# Power_Converter.net
KiCad netlist of a schematic drawn in Altium Designer
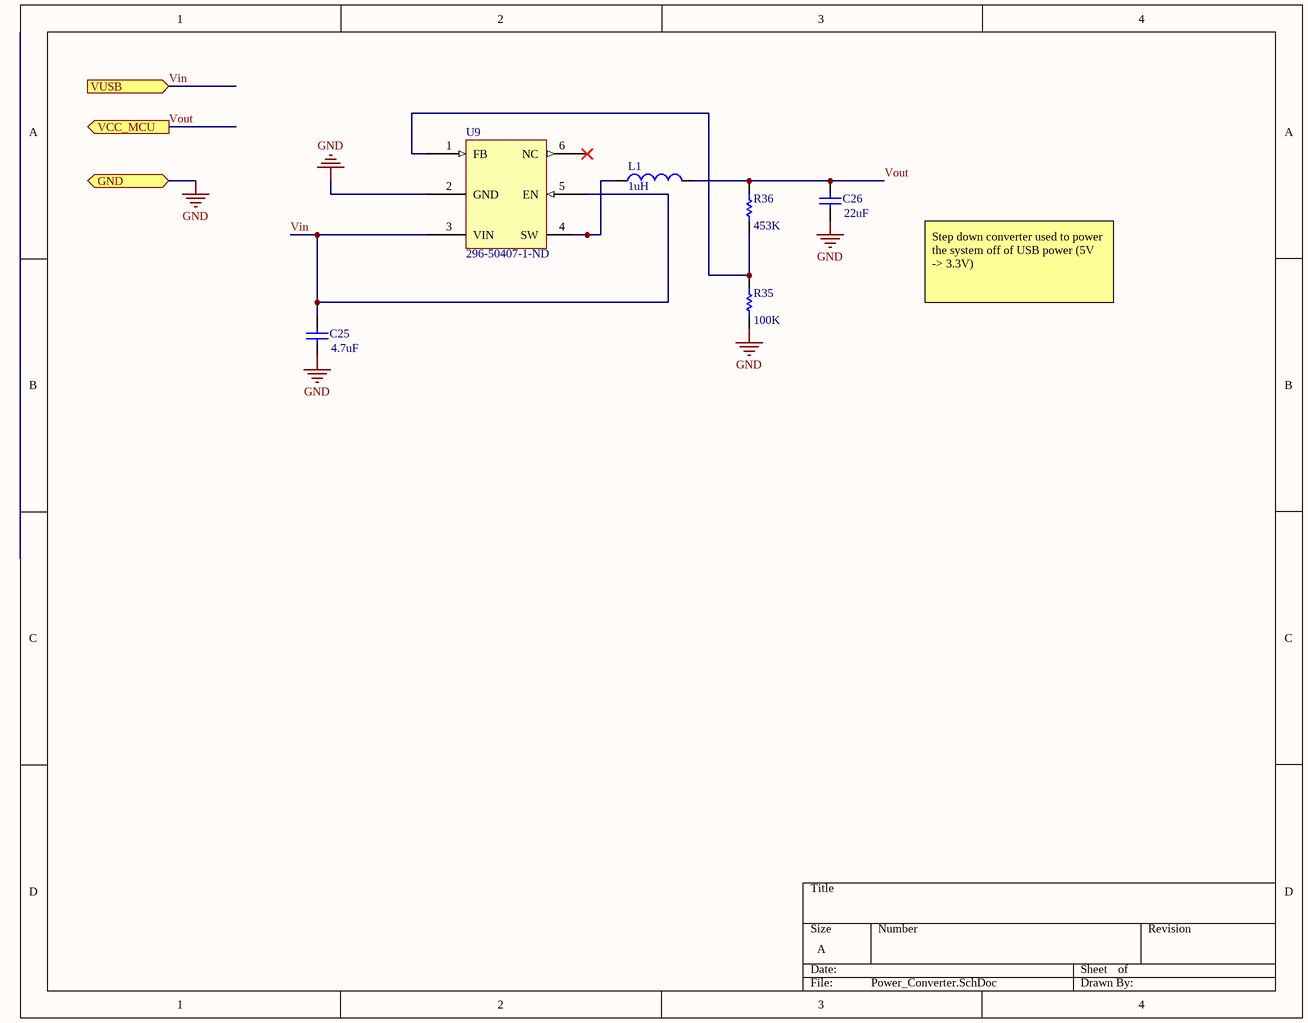
[diagram p0: Power_Converter.SchDoc]

(export (version "E")
  (design (tool "Eeschema 10.0.6"))
  (components
    (comp (ref "C25")
      (value "4.7uF")
      (footprint "1608[0603]")
      (description "4.7 uF 10V 0603")
      (fields (field (name "Comment") "Cap") (field (name "PUBLISHER") "Altium Limited"))
      (libsource (lib "Miscellaneous Devices") (part "Cap"))
    )
    (comp (ref "C26")
      (value "22uF")
      (footprint "1608[0603]")
      (description "Capacitor")
      (fields (field (name "Comment") "Cap") (field (name "PUBLISHER") "Altium Limited"))
      (libsource (lib "Miscellaneous Devices") (part "Cap"))
    )
    (comp (ref "L1")
      (value "1uH")
      (footprint "DFE252012F")
      (description "Inductor")
      (fields (field (name "PUBLISHER") "Altium Limited"))
      (libsource (lib "Miscellaneous Devices") (part "Inductor"))
    )
    (comp (ref "R35")
      (value "100K")
      (footprint "0402")
      (description "Resistor")
      (fields (field (name "Comment") "Res1") (field (name "PUBLISHER") "Altium Limited"))
      (libsource (lib "Miscellaneous Devices") (part "Res1"))
    )
    (comp (ref "R36")
      (value "453K")
      (footprint "6-0805_L")
      (description "Resistor")
      (fields (field (name "Comment") "Res1") (field (name "PUBLISHER") "Altium Limited"))
      (libsource (lib "Miscellaneous Devices") (part "Res1"))
    )
    (comp (ref "U9")
      (value "TLV62568DRL")
      (footprint "TLV62568-SOT563")
      (description "This is a buck/boost converter designed by Texas Instruments")
      (fields
        (field (name "MANUFACTURER") "Texas Instruments")
        (field (name "MANUFACTURER PART NUMBER") "TLV62568ADRLR")
        (field (name "SUPPLIER PART NUMBER 1") "296-50407-1-ND")
      )
      (libsource (lib "altium-import") (part "root_0_TLV62568ADRL_"))
    )
  )
  (nets
    (net (code "1") (name "/Vin") (class "Default")
      (node (ref "C25") (pin "2") (pinfunction "2_2") (pintype "passive"))
      (node (ref "U9") (pin "3") (pinfunction "VIN_3") (pintype "power_in"))
      (node (ref "U9") (pin "5") (pinfunction "EN_5") (pintype "input"))
    )
    (net (code "2") (name "/Vout") (class "Default")
      (node (ref "C26") (pin "2") (pinfunction "2_2") (pintype "passive"))
      (node (ref "L1") (pin "2") (pinfunction "2_2") (pintype "passive"))
      (node (ref "R36") (pin "2") (pinfunction "2_2") (pintype "passive"))
    )
    (net (code "3") (name "GND") (class "Default")
      (node (ref "C25") (pin "1") (pinfunction "1_1") (pintype "passive"))
      (node (ref "C26") (pin "1") (pinfunction "1_1") (pintype "passive"))
      (node (ref "R35") (pin "1") (pinfunction "1_1") (pintype "passive"))
      (node (ref "U9") (pin "2") (pinfunction "GND_2") (pintype "power_in"))
    )
    (net (code "4") (name "Net-(U9-FB)") (class "Default")
      (node (ref "R35") (pin "2") (pinfunction "2_2") (pintype "passive"))
      (node (ref "R36") (pin "1") (pinfunction "1_1") (pintype "passive"))
      (node (ref "U9") (pin "1") (pinfunction "FB_1") (pintype "input"))
    )
    (net (code "5") (name "Net-(U9-SW)") (class "Default")
      (node (ref "L1") (pin "1") (pinfunction "1_1") (pintype "passive"))
      (node (ref "U9") (pin "4") (pinfunction "SW_4") (pintype "power_in"))
    )
    (net (code "6") (name "unconnected-(U9-NC-Pad6)") (class "Default")
      (node (ref "U9") (pin "6") (pinfunction "NC_6") (pintype "output+no_connect"))
    )
  )
)
